# Power.net
KiCad netlist of a schematic drawn in Altium Designer
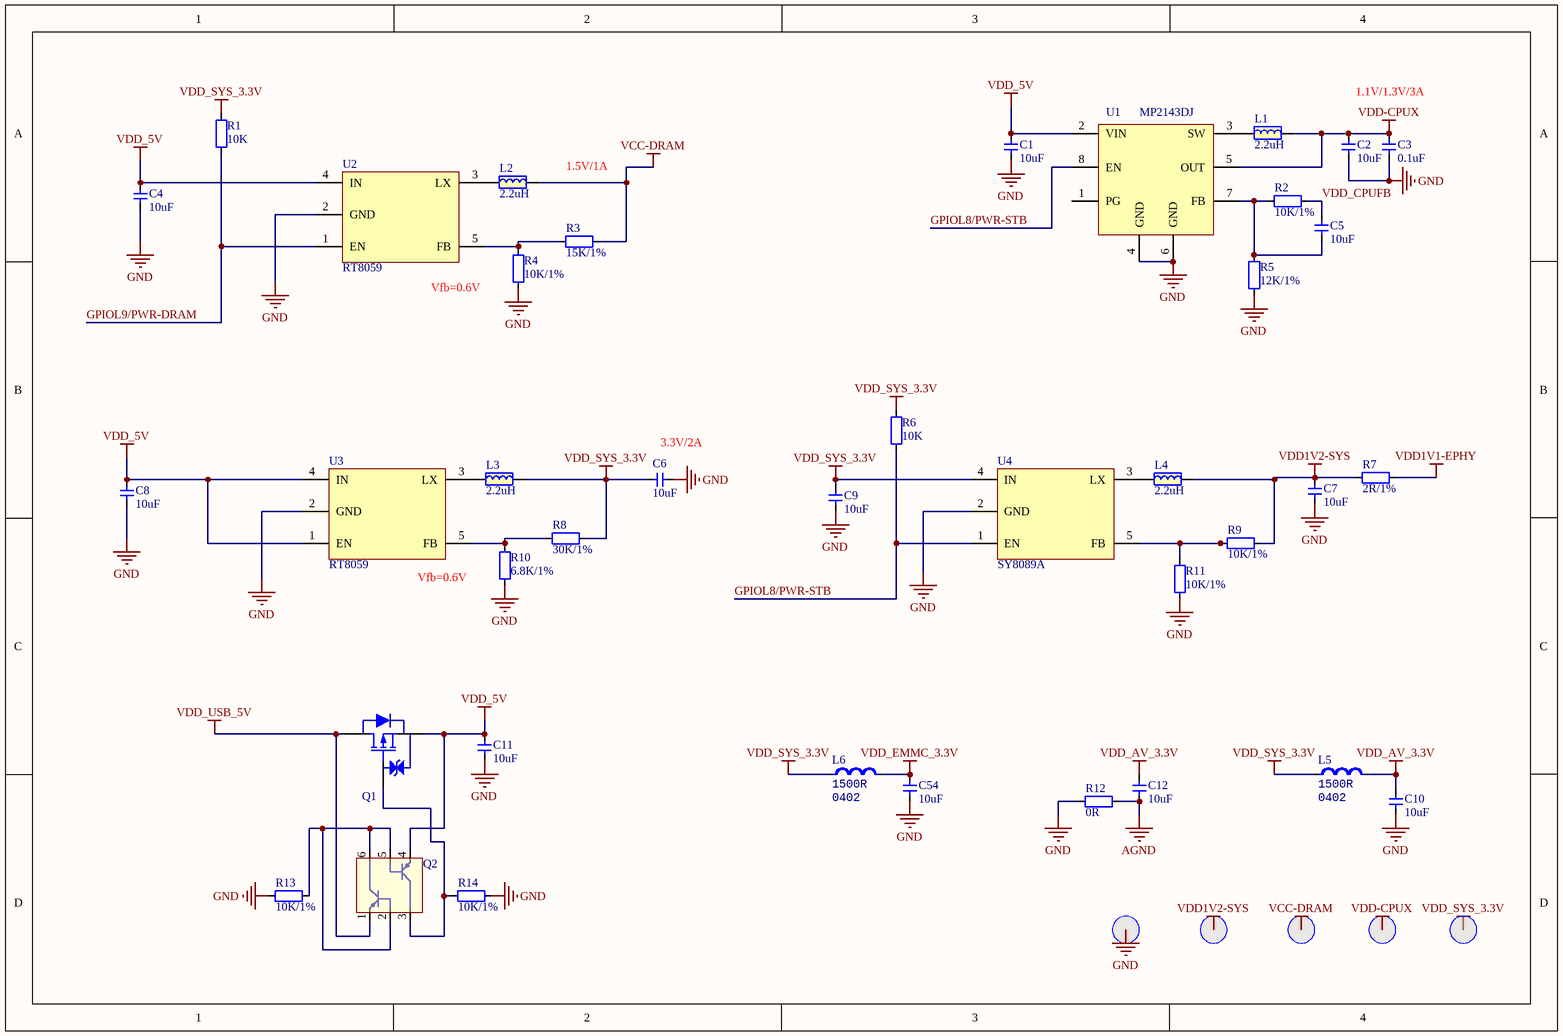
[diagram p0: Power.SchDoc]

(export (version "E")
  (design (tool "Eeschema 10.0.6"))
  (components
    (comp (ref "C1")
      (value "10uF")
      (footprint "CAP_0402")
      (description "Capacitor")
      (libsource (lib "MyPcbLib") (part "电容-0402"))
    )
    (comp (ref "C2")
      (value "10uF")
      (footprint "CAP_0402")
      (description "Capacitor")
      (libsource (lib "MyPcbLib") (part "电容-0402"))
    )
    (comp (ref "C3")
      (value "0.1uF")
      (footprint "CAP_0402")
      (description "Capacitor")
      (libsource (lib "MyPcbLib") (part "电容-0402"))
    )
    (comp (ref "C4")
      (value "10uF")
      (footprint "CAP_0402")
      (description "Capacitor")
      (libsource (lib "MyPcbLib") (part "电容-0402"))
    )
    (comp (ref "C5")
      (value "10uF")
      (footprint "CAP_0402")
      (description "Capacitor")
      (libsource (lib "MyPcbLib") (part "电容-0402"))
    )
    (comp (ref "C6")
      (value "10uF")
      (footprint "CAP_0402")
      (description "Capacitor")
      (libsource (lib "MyPcbLib") (part "电容-0402"))
    )
    (comp (ref "C7")
      (value "10uF")
      (footprint "CAP_0402")
      (description "Capacitor")
      (libsource (lib "MyPcbLib") (part "电容-0402"))
    )
    (comp (ref "C8")
      (value "10uF")
      (footprint "CAP_0402")
      (description "Capacitor")
      (libsource (lib "MyPcbLib") (part "电容-0402"))
    )
    (comp (ref "C9")
      (value "10uF")
      (footprint "CAP_0402")
      (description "Capacitor")
      (libsource (lib "MyPcbLib") (part "电容-0402"))
    )
    (comp (ref "C10")
      (value "10uF")
      (footprint "CAP_0402")
      (description "Capacitor")
      (libsource (lib "MyPcbLib") (part "电容-0402"))
    )
    (comp (ref "C11")
      (value "10uF")
      (footprint "CAP_0402")
      (description "Capacitor")
      (libsource (lib "MyPcbLib") (part "电容-0402"))
    )
    (comp (ref "C12")
      (value "10uF")
      (footprint "CAP_0402")
      (description "Capacitor")
      (libsource (lib "MyPcbLib") (part "电容-0402"))
    )
    (comp (ref "C54")
      (value "10uF")
      (footprint "CAP_0402")
      (description "Capacitor")
      (libsource (lib "MyPcbLib") (part "电容-0402"))
    )
    (comp (ref "L1")
      (value "2.2uH")
      (footprint "2520-L")
      (description "磁珠")
      (libsource (lib "MyPcbLib") (part "电感-2520"))
    )
    (comp (ref "L2")
      (value "2.2uH")
      (footprint "2520-L")
      (description "磁珠")
      (libsource (lib "MyPcbLib") (part "电感-2520"))
    )
    (comp (ref "L3")
      (value "2.2uH")
      (footprint "2520-L")
      (description "磁珠")
      (libsource (lib "MyPcbLib") (part "电感-2520"))
    )
    (comp (ref "L4")
      (value "2.2uH")
      (footprint "2520-L")
      (description "磁珠")
      (libsource (lib "MyPcbLib") (part "电感-2520"))
    )
    (comp (ref "L5")
      (value "1500R")
      (footprint "IND_0402")
      (description "Inductor")
      (fields (field (name "TYPE") "0402") (field (name "Comment") "H0402"))
      (libsource (lib "KitSprout") (part "Ind_0402"))
    )
    (comp (ref "L6")
      (value "1500R")
      (footprint "IND_0402")
      (description "Inductor")
      (fields (field (name "TYPE") "0402") (field (name "Comment") "H0402"))
      (libsource (lib "KitSprout") (part "Ind_0402"))
    )
    (comp (ref "Q1")
      (value "AO3415A")
      (footprint "SOT23-3")
      (description "MOSFET")
      (fields (field (name "PUBLISHER") "Altium Limited"))
      (libsource (lib "MyPcbLib") (part "AO3415A"))
    )
    (comp (ref "Q2")
      (value "BCM856BS")
      (footprint "SOT363-6")
      (description "Transistor")
      (libsource (lib "MyPcbLib") (part "BCM856BS"))
    )
    (comp (ref "R1")
      (value "10K")
      (footprint "RES_0402")
      (description "Resistor")
      (libsource (lib "") (part "电阻-0402_2"))
    )
    (comp (ref "R2")
      (value "10K/1%")
      (footprint "RES_0402")
      (description "Resistor")
      (libsource (lib "MyPcbLib") (part "电阻-0402"))
    )
    (comp (ref "R3")
      (value "15K/1%")
      (footprint "RES_0402")
      (description "Resistor")
      (libsource (lib "") (part "电阻-0402_1"))
    )
    (comp (ref "R4")
      (value "10K/1%")
      (footprint "RES_0402")
      (description "Resistor")
      (libsource (lib "") (part "电阻-0402_2"))
    )
    (comp (ref "R5")
      (value "12K/1%")
      (footprint "RES_0402")
      (description "Resistor")
      (libsource (lib "") (part "电阻-0402_2"))
    )
    (comp (ref "R6")
      (value "10K")
      (footprint "RES_0402")
      (description "Resistor")
      (libsource (lib "") (part "电阻-0402_2"))
    )
    (comp (ref "R7")
      (value "2R/1%")
      (footprint "RES_0402")
      (description "Resistor")
      (libsource (lib "MyPcbLib") (part "电阻-0402"))
    )
    (comp (ref "R8")
      (value "30K/1%")
      (footprint "RES_0402")
      (description "Resistor")
      (libsource (lib "") (part "电阻-0402_1"))
    )
    (comp (ref "R9")
      (value "10K/1%")
      (footprint "RES_0402")
      (description "Resistor")
      (libsource (lib "MyPcbLib") (part "电阻-0402"))
    )
    (comp (ref "R10")
      (value "6.8K/1%")
      (footprint "RES_0402")
      (description "Resistor")
      (libsource (lib "") (part "电阻-0402_2"))
    )
    (comp (ref "R11")
      (value "10K/1%")
      (footprint "RES_0402")
      (description "Resistor")
      (libsource (lib "") (part "电阻-0402_2"))
    )
    (comp (ref "R12")
      (value "0R")
      (footprint "RES_0402")
      (description "Resistor")
      (libsource (lib "") (part "电阻-0402_1"))
    )
    (comp (ref "R13")
      (value "10K/1%")
      (footprint "RES_0402")
      (description "Resistor")
      (libsource (lib "MyPcbLib") (part "电阻-0402"))
    )
    (comp (ref "R14")
      (value "10K/1%")
      (footprint "RES_0402")
      (description "Resistor")
      (libsource (lib "MyPcbLib") (part "电阻-0402"))
    )
    (comp (ref "T1") (value "测试点") (footprint "TEST_PT") (libsource (lib "MyPcbLib") (part "测试点")))
    (comp (ref "T2") (value "测试点") (footprint "TEST_PT") (libsource (lib "MyPcbLib") (part "测试点")))
    (comp (ref "T3") (value "测试点") (footprint "TEST_PT") (libsource (lib "MyPcbLib") (part "测试点")))
    (comp (ref "T4") (value "测试点") (footprint "TEST_PT") (libsource (lib "MyPcbLib") (part "测试点")))
    (comp (ref "T5") (value "测试点") (footprint "TEST_PT") (libsource (lib "MyPcbLib") (part "测试点")))
    (comp (ref "U1")
      (value "MP2143DJ")
      (footprint "SOT23-8")
      (description "LDO")
      (libsource (lib "MyPcbLib") (part "MP2143DJ"))
    )
    (comp (ref "U2")
      (value "RT8059")
      (footprint "SOT23-5")
      (description "LDO")
      (libsource (lib "MyPcbLib") (part "RT8059"))
    )
    (comp (ref "U3")
      (value "RT8059")
      (footprint "SOT23-5")
      (description "LDO")
      (libsource (lib "MyPcbLib") (part "RT8059"))
    )
    (comp (ref "U4")
      (value "SY8089A")
      (footprint "SOT23-5")
      (description "LDO")
      (libsource (lib "MyPcbLib") (part "SY8089A"))
    )
  )
  (nets
    (net (code "1") (name "/GPIOL8{slash}PWR-STB") (class "Default")
      (node (ref "R6") (pin "1") (pinfunction "1_1") (pintype "passive"))
      (node (ref "U1") (pin "8") (pinfunction "EN_8") (pintype "passive"))
      (node (ref "U4") (pin "1") (pinfunction "EN_1") (pintype "passive"))
    )
    (net (code "2") (name "/GPIOL9{slash}PWR-DRAM") (class "Default")
      (node (ref "R1") (pin "1") (pinfunction "1_1") (pintype "passive"))
      (node (ref "U2") (pin "1") (pinfunction "EN_1") (pintype "passive"))
    )
    (net (code "3") (name "/VDD_CPUFB") (class "Default")
      (node (ref "C5") (pin "2") (pinfunction "2_2") (pintype "passive"))
      (node (ref "R2") (pin "2") (pinfunction "2_2") (pintype "passive"))
    )
    (net (code "4") (name "AGND") (class "Default")
      (node (ref "C12") (pin "1") (pinfunction "1_1") (pintype "passive"))
      (node (ref "R12") (pin "1") (pinfunction "1_1") (pintype "passive"))
    )
    (net (code "5") (name "GND") (class "Default")
      (node (ref "C1") (pin "1") (pinfunction "1_1") (pintype "passive"))
      (node (ref "C10") (pin "1") (pinfunction "1_1") (pintype "passive"))
      (node (ref "C11") (pin "1") (pinfunction "1_1") (pintype "passive"))
      (node (ref "C2") (pin "1") (pinfunction "1_1") (pintype "passive"))
      (node (ref "C3") (pin "1") (pinfunction "1_1") (pintype "passive"))
      (node (ref "C4") (pin "1") (pinfunction "1_1") (pintype "passive"))
      (node (ref "C54") (pin "1") (pinfunction "1_1") (pintype "passive"))
      (node (ref "C6") (pin "1") (pinfunction "1_1") (pintype "passive"))
      (node (ref "C7") (pin "1") (pinfunction "1_1") (pintype "passive"))
      (node (ref "C8") (pin "1") (pinfunction "1_1") (pintype "passive"))
      (node (ref "C9") (pin "1") (pinfunction "1_1") (pintype "passive"))
      (node (ref "R10") (pin "1") (pinfunction "1_1") (pintype "passive"))
      (node (ref "R11") (pin "1") (pinfunction "1_1") (pintype "passive"))
      (node (ref "R12") (pin "2") (pinfunction "2_2") (pintype "passive"))
      (node (ref "R13") (pin "1") (pinfunction "1_1") (pintype "passive"))
      (node (ref "R14") (pin "2") (pinfunction "2_2") (pintype "passive"))
      (node (ref "R4") (pin "1") (pinfunction "1_1") (pintype "passive"))
      (node (ref "R5") (pin "1") (pinfunction "1_1") (pintype "passive"))
      (node (ref "T1") (pin "0") (pinfunction "0_0") (pintype "passive"))
      (node (ref "U1") (pin "4") (pinfunction "GND_4") (pintype "passive"))
      (node (ref "U1") (pin "6") (pinfunction "GND_6") (pintype "passive"))
      (node (ref "U2") (pin "2") (pinfunction "GND_2") (pintype "passive"))
      (node (ref "U3") (pin "2") (pinfunction "GND_2") (pintype "passive"))
      (node (ref "U4") (pin "2") (pinfunction "GND_2") (pintype "passive"))
    )
    (net (code "6") (name "Net-(Q1-G)") (class "Default")
      (node (ref "Q1") (pin "1") (pinfunction "G_1") (pintype "passive"))
      (node (ref "Q2") (pin "3") (pintype "passive"))
      (node (ref "R14") (pin "1") (pinfunction "1_1") (pintype "passive"))
    )
    (net (code "7") (name "Net-(Q2-Pad2)") (class "Default")
      (node (ref "Q2") (pin "2") (pintype "passive"))
      (node (ref "Q2") (pin "5") (pintype "passive"))
      (node (ref "Q2") (pin "6") (pintype "passive"))
      (node (ref "R13") (pin "2") (pinfunction "2_2") (pintype "passive"))
    )
    (net (code "8") (name "Net-(U1-FB)") (class "Default")
      (node (ref "C5") (pin "1") (pinfunction "1_1") (pintype "passive"))
      (node (ref "R2") (pin "1") (pinfunction "1_1") (pintype "passive"))
      (node (ref "R5") (pin "2") (pinfunction "2_2") (pintype "passive"))
      (node (ref "U1") (pin "7") (pinfunction "FB_7") (pintype "passive"))
    )
    (net (code "9") (name "Net-(U1-SW)") (class "Default")
      (node (ref "L1") (pin "1") (pintype "passive"))
      (node (ref "U1") (pin "3") (pinfunction "SW_3") (pintype "passive"))
    )
    (net (code "10") (name "Net-(U2-FB)") (class "Default")
      (node (ref "R3") (pin "2") (pinfunction "2_2") (pintype "passive"))
      (node (ref "R4") (pin "2") (pinfunction "2_2") (pintype "passive"))
      (node (ref "U2") (pin "5") (pinfunction "FB_5") (pintype "passive"))
    )
    (net (code "11") (name "Net-(U2-LX)") (class "Default")
      (node (ref "L2") (pin "1") (pintype "passive"))
      (node (ref "U2") (pin "3") (pinfunction "LX_3") (pintype "passive"))
    )
    (net (code "12") (name "Net-(U3-FB)") (class "Default")
      (node (ref "R10") (pin "2") (pinfunction "2_2") (pintype "passive"))
      (node (ref "R8") (pin "2") (pinfunction "2_2") (pintype "passive"))
      (node (ref "U3") (pin "5") (pinfunction "FB_5") (pintype "passive"))
    )
    (net (code "13") (name "Net-(U3-LX)") (class "Default")
      (node (ref "L3") (pin "1") (pintype "passive"))
      (node (ref "U3") (pin "3") (pinfunction "LX_3") (pintype "passive"))
    )
    (net (code "14") (name "Net-(U4-FB)") (class "Default")
      (node (ref "R11") (pin "2") (pinfunction "2_2") (pintype "passive"))
      (node (ref "R9") (pin "1") (pinfunction "1_1") (pintype "passive"))
      (node (ref "U4") (pin "5") (pinfunction "FB_5") (pintype "passive"))
    )
    (net (code "15") (name "Net-(U4-LX)") (class "Default")
      (node (ref "L4") (pin "1") (pintype "passive"))
      (node (ref "U4") (pin "3") (pinfunction "LX_3") (pintype "passive"))
    )
    (net (code "16") (name "VCC-DRAM") (class "Default")
      (node (ref "L2") (pin "2") (pinfunction "2_2") (pintype "passive"))
      (node (ref "R3") (pin "1") (pinfunction "1_1") (pintype "passive"))
      (node (ref "T3") (pin "0") (pinfunction "0_0") (pintype "passive"))
    )
    (net (code "17") (name "VDD-CPUX") (class "Default")
      (node (ref "C2") (pin "2") (pinfunction "2_2") (pintype "passive"))
      (node (ref "C3") (pin "2") (pinfunction "2_2") (pintype "passive"))
      (node (ref "L1") (pin "2") (pinfunction "2_2") (pintype "passive"))
      (node (ref "T4") (pin "0") (pinfunction "0_0") (pintype "passive"))
      (node (ref "U1") (pin "5") (pinfunction "OUT_5") (pintype "passive"))
    )
    (net (code "18") (name "VDD1V1-EPHY") (class "Default")
      (node (ref "R7") (pin "2") (pinfunction "2_2") (pintype "passive"))
    )
    (net (code "19") (name "VDD1V2-SYS") (class "Default")
      (node (ref "C7") (pin "2") (pinfunction "2_2") (pintype "passive"))
      (node (ref "L4") (pin "2") (pinfunction "2_2") (pintype "passive"))
      (node (ref "R7") (pin "1") (pinfunction "1_1") (pintype "passive"))
      (node (ref "R9") (pin "2") (pinfunction "2_2") (pintype "passive"))
      (node (ref "T2") (pin "0") (pinfunction "0_0") (pintype "passive"))
    )
    (net (code "20") (name "VDD_5V") (class "Default")
      (node (ref "C1") (pin "2") (pinfunction "2_2") (pintype "passive"))
      (node (ref "C11") (pin "2") (pinfunction "2_2") (pintype "passive"))
      (node (ref "C4") (pin "2") (pinfunction "2_2") (pintype "passive"))
      (node (ref "C8") (pin "2") (pinfunction "2_2") (pintype "passive"))
      (node (ref "Q1") (pin "2") (pinfunction "S_2") (pintype "passive"))
      (node (ref "Q2") (pin "4") (pintype "passive"))
      (node (ref "U1") (pin "2") (pinfunction "VIN_2") (pintype "passive"))
      (node (ref "U2") (pin "4") (pinfunction "IN_4") (pintype "passive"))
      (node (ref "U3") (pin "1") (pinfunction "EN_1") (pintype "passive"))
      (node (ref "U3") (pin "4") (pinfunction "IN_4") (pintype "passive"))
    )
    (net (code "21") (name "VDD_AV_3.3V") (class "Default")
      (node (ref "C10") (pin "2") (pinfunction "2_2") (pintype "passive"))
      (node (ref "C12") (pin "2") (pinfunction "2_2") (pintype "passive"))
      (node (ref "L5") (pin "2") (pinfunction "2_2") (pintype "passive"))
    )
    (net (code "22") (name "VDD_EMMC_3.3V") (class "Default")
      (node (ref "C54") (pin "2") (pinfunction "2_2") (pintype "passive"))
      (node (ref "L6") (pin "2") (pinfunction "2_2") (pintype "passive"))
    )
    (net (code "23") (name "VDD_SYS_3.3V") (class "Default")
      (node (ref "C6") (pin "2") (pinfunction "2_2") (pintype "passive"))
      (node (ref "C9") (pin "2") (pinfunction "2_2") (pintype "passive"))
      (node (ref "L3") (pin "2") (pinfunction "2_2") (pintype "passive"))
      (node (ref "L5") (pin "1") (pinfunction "1_1") (pintype "passive"))
      (node (ref "L6") (pin "1") (pinfunction "1_1") (pintype "passive"))
      (node (ref "R1") (pin "2") (pinfunction "2_2") (pintype "passive"))
      (node (ref "R6") (pin "2") (pinfunction "2_2") (pintype "passive"))
      (node (ref "R8") (pin "1") (pinfunction "1_1") (pintype "passive"))
      (node (ref "T5") (pin "0") (pinfunction "0_0") (pintype "passive"))
      (node (ref "U4") (pin "4") (pinfunction "IN_4") (pintype "passive"))
    )
    (net (code "24") (name "VDD_USB_5V") (class "Default")
      (node (ref "Q1") (pin "3") (pinfunction "D_3") (pintype "passive"))
      (node (ref "Q2") (pin "1") (pintype "passive"))
    )
    (net (code "25") (name "unconnected-(U1-PG-Pad1)") (class "Default")
      (node (ref "U1") (pin "1") (pinfunction "PG_1") (pintype "passive"))
    )
  )
)
